# TT7-F_v1_5.net
KiCad netlist of a schematic drawn in EAGLE
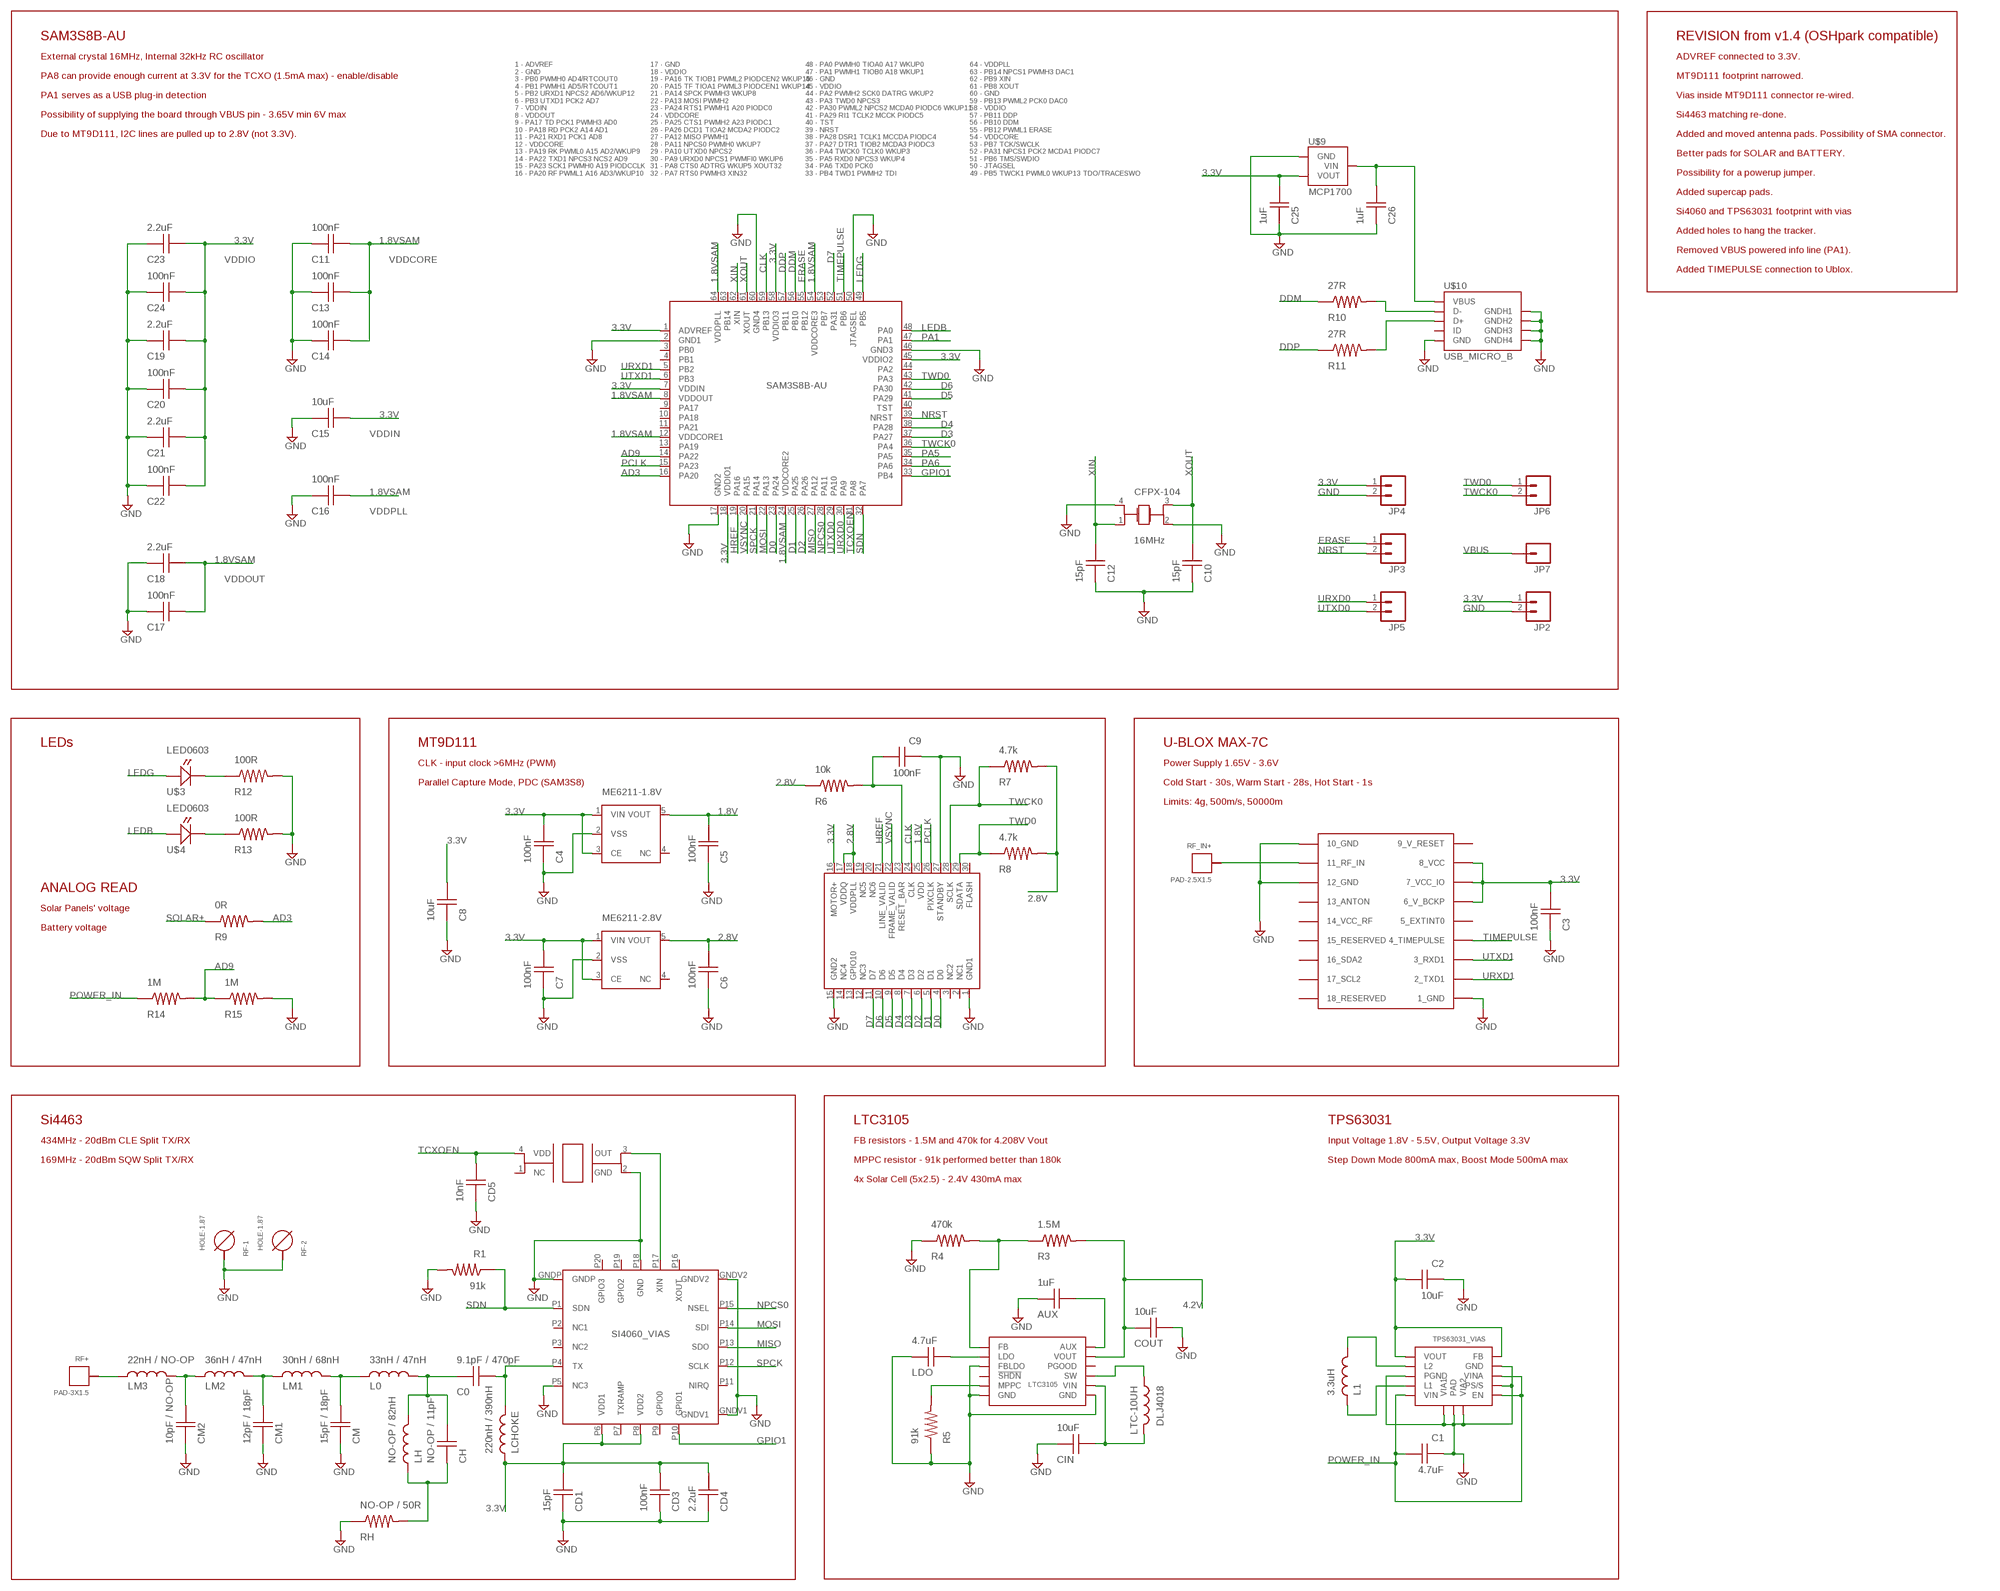
[diagram p0: schematic, sheet 1]

(export (version "E")
  (design (tool "Eeschema 10.0.6"))
  (components
    (comp (ref "AUX")
      (value "1uF")
      (footprint "eagle-import:CAP0603")
      (libsource (lib "eagle-import") (part "CAP0603"))
    )
    (comp (ref "C0")
      (value "9.1pF / 470pF")
      (footprint "eagle-import:CAP0402")
      (libsource (lib "eagle-import") (part "CAP0402"))
    )
    (comp (ref "C1")
      (value "4.7uF")
      (footprint "eagle-import:CAP0603")
      (libsource (lib "eagle-import") (part "CAP0603"))
    )
    (comp (ref "C2")
      (value "10uF")
      (footprint "eagle-import:CAP0805")
      (libsource (lib "eagle-import") (part "CAP0805"))
    )
    (comp (ref "C3")
      (value "100nF")
      (footprint "eagle-import:CAP0402")
      (libsource (lib "eagle-import") (part "CAP0402"))
    )
    (comp (ref "C4")
      (value "100nF")
      (footprint "eagle-import:CAP0402")
      (libsource (lib "eagle-import") (part "CAP0402"))
    )
    (comp (ref "C5")
      (value "100nF")
      (footprint "eagle-import:CAP0402")
      (libsource (lib "eagle-import") (part "CAP0402"))
    )
    (comp (ref "C6")
      (value "100nF")
      (footprint "eagle-import:CAP0402")
      (libsource (lib "eagle-import") (part "CAP0402"))
    )
    (comp (ref "C7")
      (value "100nF")
      (footprint "eagle-import:CAP0402")
      (libsource (lib "eagle-import") (part "CAP0402"))
    )
    (comp (ref "C8")
      (value "10uF")
      (footprint "eagle-import:CAP0805")
      (libsource (lib "eagle-import") (part "CAP0805"))
    )
    (comp (ref "C9")
      (value "100nF")
      (footprint "eagle-import:CAP0402")
      (libsource (lib "eagle-import") (part "CAP0402"))
    )
    (comp (ref "C10")
      (value "15pF")
      (footprint "eagle-import:CAP0402")
      (libsource (lib "eagle-import") (part "CAP0402"))
    )
    (comp (ref "C11")
      (value "100nF")
      (footprint "eagle-import:CAP0402")
      (libsource (lib "eagle-import") (part "CAP0402"))
    )
    (comp (ref "C12")
      (value "15pF")
      (footprint "eagle-import:CAP0402")
      (libsource (lib "eagle-import") (part "CAP0402"))
    )
    (comp (ref "C13")
      (value "100nF")
      (footprint "eagle-import:CAP0402")
      (libsource (lib "eagle-import") (part "CAP0402"))
    )
    (comp (ref "C14")
      (value "100nF")
      (footprint "eagle-import:CAP0402")
      (libsource (lib "eagle-import") (part "CAP0402"))
    )
    (comp (ref "C15")
      (value "10uF")
      (footprint "eagle-import:CAP0603")
      (libsource (lib "eagle-import") (part "CAP0603"))
    )
    (comp (ref "C16")
      (value "100nF")
      (footprint "eagle-import:CAP0402")
      (libsource (lib "eagle-import") (part "CAP0402"))
    )
    (comp (ref "C17")
      (value "100nF")
      (footprint "eagle-import:CAP0402")
      (libsource (lib "eagle-import") (part "CAP0402"))
    )
    (comp (ref "C18")
      (value "2.2uF")
      (footprint "eagle-import:CAP0402")
      (libsource (lib "eagle-import") (part "CAP0402"))
    )
    (comp (ref "C19")
      (value "2.2uF")
      (footprint "eagle-import:CAP0402")
      (libsource (lib "eagle-import") (part "CAP0402"))
    )
    (comp (ref "C20")
      (value "100nF")
      (footprint "eagle-import:CAP0402")
      (libsource (lib "eagle-import") (part "CAP0402"))
    )
    (comp (ref "C21")
      (value "2.2uF")
      (footprint "eagle-import:CAP0402")
      (libsource (lib "eagle-import") (part "CAP0402"))
    )
    (comp (ref "C22")
      (value "100nF")
      (footprint "eagle-import:CAP0402")
      (libsource (lib "eagle-import") (part "CAP0402"))
    )
    (comp (ref "C23")
      (value "2.2uF")
      (footprint "eagle-import:CAP0402")
      (libsource (lib "eagle-import") (part "CAP0402"))
    )
    (comp (ref "C24")
      (value "100nF")
      (footprint "eagle-import:CAP0402")
      (libsource (lib "eagle-import") (part "CAP0402"))
    )
    (comp (ref "C25")
      (value "1uF")
      (footprint "eagle-import:CAP0603")
      (libsource (lib "eagle-import") (part "CAP0603"))
    )
    (comp (ref "C26")
      (value "1uF")
      (footprint "eagle-import:CAP0603")
      (libsource (lib "eagle-import") (part "CAP0603"))
    )
    (comp (ref "CD1")
      (value "15pF")
      (footprint "eagle-import:CAP0402")
      (libsource (lib "eagle-import") (part "CAP0402"))
    )
    (comp (ref "CD3")
      (value "100nF")
      (footprint "eagle-import:CAP0402")
      (libsource (lib "eagle-import") (part "CAP0402"))
    )
    (comp (ref "CD4")
      (value "2.2uF")
      (footprint "eagle-import:CAP0402")
      (libsource (lib "eagle-import") (part "CAP0402"))
    )
    (comp (ref "CD5")
      (value "10nF")
      (footprint "eagle-import:CAP0402")
      (libsource (lib "eagle-import") (part "CAP0402"))
    )
    (comp (ref "CFPX-104")
      (value "16MHz")
      (footprint "eagle-import:CFPX-104")
      (libsource (lib "eagle-import") (part "CFPX-104"))
    )
    (comp (ref "CH")
      (value "NO-OP / 11pF")
      (footprint "eagle-import:CAP0402")
      (libsource (lib "eagle-import") (part "CAP0402"))
    )
    (comp (ref "CIN")
      (value "10uF")
      (footprint "eagle-import:CAP0603")
      (libsource (lib "eagle-import") (part "CAP0603"))
    )
    (comp (ref "CM")
      (value "15pF / 18pF")
      (footprint "eagle-import:CAP0402")
      (libsource (lib "eagle-import") (part "CAP0402"))
    )
    (comp (ref "CM1")
      (value "12pF / 18pF")
      (footprint "eagle-import:CAP0402")
      (libsource (lib "eagle-import") (part "CAP0402"))
    )
    (comp (ref "CM2")
      (value "10pF / NO-OP")
      (footprint "eagle-import:CAP0402")
      (libsource (lib "eagle-import") (part "CAP0402"))
    )
    (comp (ref "COUT")
      (value "10uF")
      (footprint "eagle-import:CAP0805")
      (libsource (lib "eagle-import") (part "CAP0805"))
    )
    (comp (ref "JP2")
      (value "M021X02_NO_SILK")
      (footprint "eagle-import:1X02_NO_SILK")
      (libsource (lib "eagle-import") (part "M021X02_NO_SILK"))
    )
    (comp (ref "JP3")
      (value "M021X02_NO_SILK")
      (footprint "eagle-import:1X02_NO_SILK")
      (libsource (lib "eagle-import") (part "M021X02_NO_SILK"))
    )
    (comp (ref "JP4")
      (value "M021X02_NO_SILK")
      (footprint "eagle-import:1X02_NO_SILK")
      (libsource (lib "eagle-import") (part "M021X02_NO_SILK"))
    )
    (comp (ref "JP5")
      (value "M021X02_NO_SILK")
      (footprint "eagle-import:1X02_NO_SILK")
      (libsource (lib "eagle-import") (part "M021X02_NO_SILK"))
    )
    (comp (ref "JP6")
      (value "M021X02_NO_SILK")
      (footprint "eagle-import:1X02_NO_SILK")
      (libsource (lib "eagle-import") (part "M021X02_NO_SILK"))
    )
    (comp (ref "JP7")
      (value "M01PTH_NO_SILK_YES_STOP")
      (footprint "eagle-import:1X01_NO_SILK")
      (libsource (lib "eagle-import") (part "M01PTH_NO_SILK_YES_STOP"))
    )
    (comp (ref "L0")
      (value "33nH / 47nH")
      (footprint "eagle-import:IND0402")
      (libsource (lib "eagle-import") (part "IND0402"))
    )
    (comp (ref "L1")
      (value "3.3uH")
      (footprint "eagle-import:DLJ3015")
      (libsource (lib "eagle-import") (part "DLJ3015"))
    )
    (comp (ref "LCHOKE")
      (value "220nH / 390nH")
      (footprint "eagle-import:IND0402")
      (libsource (lib "eagle-import") (part "IND0402"))
    )
    (comp (ref "LDO")
      (value "4.7uF")
      (footprint "eagle-import:CAP0603")
      (libsource (lib "eagle-import") (part "CAP0603"))
    )
    (comp (ref "LH")
      (value "NO-OP / 82nH")
      (footprint "eagle-import:IND0402")
      (libsource (lib "eagle-import") (part "IND0402"))
    )
    (comp (ref "LM1")
      (value "30nH / 68nH")
      (footprint "eagle-import:IND0402")
      (libsource (lib "eagle-import") (part "IND0402"))
    )
    (comp (ref "LM2")
      (value "36nH / 47nH")
      (footprint "eagle-import:IND0402")
      (libsource (lib "eagle-import") (part "IND0402"))
    )
    (comp (ref "LM3")
      (value "22nH / NO-OP")
      (footprint "eagle-import:IND0402")
      (libsource (lib "eagle-import") (part "IND0402"))
    )
    (comp (ref "LTC-10UH")
      (value "DLJ4018")
      (footprint "eagle-import:DLJ4018")
      (libsource (lib "eagle-import") (part "DLJ4018"))
    )
    (comp (ref "ME6211-1.8V")
      (value "ME6211_NEW")
      (footprint "eagle-import:ME6211_NEW")
      (libsource (lib "eagle-import") (part "ME6211_NEW"))
    )
    (comp (ref "ME6211-2.8V")
      (value "ME6211_NEW")
      (footprint "eagle-import:ME6211_NEW")
      (libsource (lib "eagle-import") (part "ME6211_NEW"))
    )
    (comp (ref "R1")
      (value "91k")
      (footprint "eagle-import:RES0402")
      (libsource (lib "eagle-import") (part "RES0402"))
    )
    (comp (ref "R3")
      (value "1.5M")
      (footprint "eagle-import:RES0402")
      (libsource (lib "eagle-import") (part "RES0402"))
    )
    (comp (ref "R4")
      (value "470k")
      (footprint "eagle-import:RES0402")
      (libsource (lib "eagle-import") (part "RES0402"))
    )
    (comp (ref "R5")
      (value "91k")
      (footprint "eagle-import:RES0402")
      (libsource (lib "eagle-import") (part "RES0402"))
    )
    (comp (ref "R6")
      (value "10k")
      (footprint "eagle-import:RES0402")
      (libsource (lib "eagle-import") (part "RES0402"))
    )
    (comp (ref "R7")
      (value "4.7k")
      (footprint "eagle-import:RES0402")
      (libsource (lib "eagle-import") (part "RES0402"))
    )
    (comp (ref "R8")
      (value "4.7k")
      (footprint "eagle-import:RES0402")
      (libsource (lib "eagle-import") (part "RES0402"))
    )
    (comp (ref "R9")
      (value "0R")
      (footprint "eagle-import:RES0402")
      (libsource (lib "eagle-import") (part "RES0402"))
    )
    (comp (ref "R10")
      (value "27R")
      (footprint "eagle-import:RES0402")
      (libsource (lib "eagle-import") (part "RES0402"))
    )
    (comp (ref "R11")
      (value "27R")
      (footprint "eagle-import:RES0402")
      (libsource (lib "eagle-import") (part "RES0402"))
    )
    (comp (ref "R12")
      (value "100R")
      (footprint "eagle-import:RES0402")
      (libsource (lib "eagle-import") (part "RES0402"))
    )
    (comp (ref "R13")
      (value "100R")
      (footprint "eagle-import:RES0402")
      (libsource (lib "eagle-import") (part "RES0402"))
    )
    (comp (ref "R14")
      (value "1M")
      (footprint "eagle-import:RES0603")
      (libsource (lib "eagle-import") (part "RES0603"))
    )
    (comp (ref "R15")
      (value "1M")
      (footprint "eagle-import:RES0603")
      (libsource (lib "eagle-import") (part "RES0603"))
    )
    (comp (ref "RF+")
      (value "PAD-3X1.5")
      (footprint "eagle-import:PAD-3X1.5")
      (libsource (lib "eagle-import") (part "PAD-3X1.5"))
    )
    (comp (ref "RF-1")
      (value "HOLE-1.87")
      (footprint "eagle-import:HOLE-1.87")
      (libsource (lib "eagle-import") (part "HOLE-1.87"))
    )
    (comp (ref "RF-2")
      (value "HOLE-1.87")
      (footprint "eagle-import:HOLE-1.87")
      (libsource (lib "eagle-import") (part "HOLE-1.87"))
    )
    (comp (ref "RF_IN+")
      (value "PAD-2.5X1.5")
      (footprint "eagle-import:PAD-2.5X1.5")
      (libsource (lib "eagle-import") (part "PAD-2.5X1.5"))
    )
    (comp (ref "RH")
      (value "NO-OP / 50R")
      (footprint "eagle-import:RES0402")
      (libsource (lib "eagle-import") (part "RES0402"))
    )
    (comp (ref "TCXO")
      (value "32MHz")
      (footprint "eagle-import:I547-2P3_TCXO")
      (libsource (lib "eagle-import") (part "I547-2P3_TCXO"))
    )
    (comp (ref "U$1")
      (value "SI4060_VIAS")
      (footprint "eagle-import:SI4060_VIAS")
      (libsource (lib "eagle-import") (part "SI4060_VIAS"))
    )
    (comp (ref "U$2")
      (value "UBLOX_MAX-7C")
      (footprint "eagle-import:UBLOX_MAX-7C")
      (libsource (lib "eagle-import") (part "UBLOX_MAX-7C"))
    )
    (comp (ref "U$3")
      (value "LED0603")
      (footprint "eagle-import:LED0603")
      (libsource (lib "eagle-import") (part "LED0603"))
    )
    (comp (ref "U$4")
      (value "LED0603")
      (footprint "eagle-import:LED0603")
      (libsource (lib "eagle-import") (part "LED0603"))
    )
    (comp (ref "U$9")
      (value "MCP1700")
      (footprint "eagle-import:MCP1700")
      (libsource (lib "eagle-import") (part "MCP1700"))
    )
    (comp (ref "U$10")
      (value "USB_MICRO_B")
      (footprint "eagle-import:USB_MICRO_B")
      (libsource (lib "eagle-import") (part "USB_MICRO_B"))
    )
    (comp (ref "U$15")
      (value "MT9D111-AVX145602-NEW")
      (footprint "eagle-import:MT9D111-AVX145602-NEW")
      (libsource (lib "eagle-import") (part "MT9D111-AVX145602-NEW"))
    )
    (comp (ref "U1")
      (value "LTC3105")
      (footprint "eagle-import:LTC3105")
      (libsource (lib "eagle-import") (part "LTC3105"))
    )
    (comp (ref "U3")
      (value "TPS63031_VIAS")
      (footprint "eagle-import:TPS63031_VIAS")
      (libsource (lib "eagle-import") (part "TPS63031_VIAS"))
    )
    (comp (ref "U4")
      (value "SAM3S8B-AU")
      (footprint "eagle-import:SAM3S8B-AU")
      (libsource (lib "eagle-import") (part "SAM3S8B-AU"))
    )
  )
  (nets
    (net (code "1") (name "/1.8V") (class "Default")
      (node (ref "C5") (pin "P$2") (pinfunction "P$2_P$2") (pintype "bidirectional"))
      (node (ref "ME6211-1.8V") (pin "5") (pinfunction "VOUT_5") (pintype "bidirectional"))
      (node (ref "U$15") (pin "25") (pinfunction "VDD_25") (pintype "bidirectional"))
    )
    (net (code "2") (name "/1.8VSAM") (class "Default")
      (node (ref "C11") (pin "P$2") (pinfunction "P$2_P$2") (pintype "bidirectional"))
      (node (ref "C13") (pin "P$2") (pinfunction "P$2_P$2") (pintype "bidirectional"))
      (node (ref "C14") (pin "P$2") (pinfunction "P$2_P$2") (pintype "bidirectional"))
      (node (ref "C16") (pin "P$2") (pinfunction "P$2_P$2") (pintype "bidirectional"))
      (node (ref "C17") (pin "P$2") (pinfunction "P$2_P$2") (pintype "bidirectional"))
      (node (ref "C18") (pin "P$2") (pinfunction "P$2_P$2") (pintype "bidirectional"))
      (node (ref "U4") (pin "12") (pinfunction "VDDCORE1_12") (pintype "bidirectional"))
      (node (ref "U4") (pin "24") (pinfunction "VDDCORE2_24") (pintype "bidirectional"))
      (node (ref "U4") (pin "54") (pinfunction "VDDCORE3_54") (pintype "bidirectional"))
      (node (ref "U4") (pin "64") (pinfunction "VDDPLL_64") (pintype "bidirectional"))
      (node (ref "U4") (pin "8") (pinfunction "VDDOUT_8") (pintype "bidirectional"))
    )
    (net (code "3") (name "/2.8V") (class "Default")
      (node (ref "C6") (pin "P$2") (pinfunction "P$2_P$2") (pintype "bidirectional"))
      (node (ref "ME6211-2.8V") (pin "5") (pinfunction "VOUT_5") (pintype "bidirectional"))
      (node (ref "R6") (pin "P$1") (pinfunction "P$1_P$1") (pintype "bidirectional"))
      (node (ref "R7") (pin "P$2") (pinfunction "P$2_P$2") (pintype "bidirectional"))
      (node (ref "R8") (pin "P$2") (pinfunction "P$2_P$2") (pintype "bidirectional"))
      (node (ref "U$15") (pin "17") (pinfunction "VDDQ_17") (pintype "bidirectional"))
      (node (ref "U$15") (pin "18") (pinfunction "VDDPLL_18") (pintype "bidirectional"))
    )
    (net (code "4") (name "/3.3V") (class "Default")
      (node (ref "C15") (pin "P$2") (pinfunction "P$2_P$2") (pintype "bidirectional"))
      (node (ref "C19") (pin "P$2") (pinfunction "P$2_P$2") (pintype "bidirectional"))
      (node (ref "C2") (pin "P$2") (pinfunction "P$2_P$2") (pintype "bidirectional"))
      (node (ref "C20") (pin "P$2") (pinfunction "P$2_P$2") (pintype "bidirectional"))
      (node (ref "C21") (pin "P$2") (pinfunction "P$2_P$2") (pintype "bidirectional"))
      (node (ref "C22") (pin "P$2") (pinfunction "P$2_P$2") (pintype "bidirectional"))
      (node (ref "C23") (pin "P$2") (pinfunction "P$2_P$2") (pintype "bidirectional"))
      (node (ref "C24") (pin "P$2") (pinfunction "P$2_P$2") (pintype "bidirectional"))
      (node (ref "C25") (pin "P$2") (pinfunction "P$2_P$2") (pintype "bidirectional"))
      (node (ref "C3") (pin "P$2") (pinfunction "P$2_P$2") (pintype "bidirectional"))
      (node (ref "C4") (pin "P$2") (pinfunction "P$2_P$2") (pintype "bidirectional"))
      (node (ref "C7") (pin "P$2") (pinfunction "P$2_P$2") (pintype "bidirectional"))
      (node (ref "C8") (pin "P$2") (pinfunction "P$2_P$2") (pintype "bidirectional"))
      (node (ref "CD1") (pin "P$2") (pinfunction "P$2_P$2") (pintype "bidirectional"))
      (node (ref "CD3") (pin "P$2") (pinfunction "P$2_P$2") (pintype "bidirectional"))
      (node (ref "CD4") (pin "P$2") (pinfunction "P$2_P$2") (pintype "bidirectional"))
      (node (ref "JP2") (pin "1") (pinfunction "1_1") (pintype "passive"))
      (node (ref "JP4") (pin "1") (pinfunction "1_1") (pintype "passive"))
      (node (ref "LCHOKE") (pin "P$1") (pinfunction "P$1_P$1") (pintype "bidirectional"))
      (node (ref "ME6211-1.8V") (pin "1") (pinfunction "VIN_1") (pintype "bidirectional"))
      (node (ref "ME6211-1.8V") (pin "3") (pinfunction "CE_3") (pintype "bidirectional"))
      (node (ref "ME6211-2.8V") (pin "1") (pinfunction "VIN_1") (pintype "bidirectional"))
      (node (ref "ME6211-2.8V") (pin "3") (pinfunction "CE_3") (pintype "bidirectional"))
      (node (ref "U$1") (pin "P6") (pinfunction "VDD1_P6") (pintype "bidirectional"))
      (node (ref "U$1") (pin "P8") (pinfunction "VDD2_P8") (pintype "bidirectional"))
      (node (ref "U$15") (pin "16") (pinfunction "MOTOR+_16") (pintype "bidirectional"))
      (node (ref "U$2") (pin "6_V_BCKP") (pinfunction "6_V_BCKP_6_V_BCKP") (pintype "bidirectional"))
      (node (ref "U$2") (pin "7_VCC_IO") (pinfunction "7_VCC_IO_7_VCC_IO") (pintype "power_in"))
      (node (ref "U$2") (pin "8_VCC") (pinfunction "8_VCC_8_VCC") (pintype "power_in"))
      (node (ref "U$9") (pin "2") (pinfunction "VOUT_2") (pintype "bidirectional"))
      (node (ref "U3") (pin "1") (pinfunction "VOUT_1") (pintype "bidirectional"))
      (node (ref "U3") (pin "10") (pinfunction "FB_10") (pintype "bidirectional"))
      (node (ref "U4") (pin "1") (pinfunction "ADVREF_1") (pintype "bidirectional"))
      (node (ref "U4") (pin "18") (pinfunction "VDDIO1_18") (pintype "bidirectional"))
      (node (ref "U4") (pin "45") (pinfunction "VDDIO2_45") (pintype "bidirectional"))
      (node (ref "U4") (pin "58") (pinfunction "VDDIO3_58") (pintype "bidirectional"))
      (node (ref "U4") (pin "7") (pinfunction "VDDIN_7") (pintype "bidirectional"))
    )
    (net (code "5") (name "/4.2V") (class "Default")
      (node (ref "COUT") (pin "P$1") (pinfunction "P$1_P$1") (pintype "bidirectional"))
      (node (ref "R3") (pin "P$2") (pinfunction "P$2_P$2") (pintype "bidirectional"))
      (node (ref "U1") (pin "11") (pinfunction "VOUT_11") (pintype "bidirectional"))
    )
    (net (code "6") (name "/9_V_RESET") (class "Default")
      (node (ref "U$2") (pin "9_V_RESET") (pinfunction "9_V_RESET_9_V_RESET") (pintype "power_in"))
    )
    (net (code "7") (name "/AD3") (class "Default")
      (node (ref "R9") (pin "P$2") (pinfunction "P$2_P$2") (pintype "bidirectional"))
      (node (ref "U4") (pin "16") (pinfunction "PA20_16") (pintype "bidirectional"))
    )
    (net (code "8") (name "/AD9") (class "Default")
      (node (ref "R14") (pin "P$2") (pinfunction "P$2_P$2") (pintype "bidirectional"))
      (node (ref "R15") (pin "P$1") (pinfunction "P$1_P$1") (pintype "bidirectional"))
      (node (ref "U4") (pin "14") (pinfunction "PA22_14") (pintype "bidirectional"))
    )
    (net (code "9") (name "/CLK") (class "Default")
      (node (ref "U$15") (pin "24") (pinfunction "CLK_24") (pintype "bidirectional"))
      (node (ref "U4") (pin "59") (pinfunction "PB13_59") (pintype "bidirectional"))
    )
    (net (code "10") (name "/D0") (class "Default")
      (node (ref "U$15") (pin "4") (pinfunction "D0_4") (pintype "bidirectional"))
      (node (ref "U4") (pin "23") (pinfunction "PA24_23") (pintype "bidirectional"))
    )
    (net (code "11") (name "/D1") (class "Default")
      (node (ref "U$15") (pin "5") (pinfunction "D1_5") (pintype "bidirectional"))
      (node (ref "U4") (pin "25") (pinfunction "PA25_25") (pintype "bidirectional"))
    )
    (net (code "12") (name "/D2") (class "Default")
      (node (ref "U$15") (pin "6") (pinfunction "D2_6") (pintype "bidirectional"))
      (node (ref "U4") (pin "26") (pinfunction "PA26_26") (pintype "bidirectional"))
    )
    (net (code "13") (name "/D3") (class "Default")
      (node (ref "U$15") (pin "7") (pinfunction "D3_7") (pintype "bidirectional"))
      (node (ref "U4") (pin "37") (pinfunction "PA27_37") (pintype "bidirectional"))
    )
    (net (code "14") (name "/D4") (class "Default")
      (node (ref "U$15") (pin "8") (pinfunction "D4_8") (pintype "bidirectional"))
      (node (ref "U4") (pin "38") (pinfunction "PA28_38") (pintype "bidirectional"))
    )
    (net (code "15") (name "/D5") (class "Default")
      (node (ref "U$15") (pin "9") (pinfunction "D5_9") (pintype "bidirectional"))
      (node (ref "U4") (pin "41") (pinfunction "PA29_41") (pintype "bidirectional"))
    )
    (net (code "16") (name "/D6") (class "Default")
      (node (ref "U$15") (pin "10") (pinfunction "D6_10") (pintype "bidirectional"))
      (node (ref "U4") (pin "42") (pinfunction "PA30_42") (pintype "bidirectional"))
    )
    (net (code "17") (name "/D7") (class "Default")
      (node (ref "U$15") (pin "11") (pinfunction "D7_11") (pintype "bidirectional"))
      (node (ref "U4") (pin "52") (pinfunction "PA31_52") (pintype "bidirectional"))
    )
    (net (code "18") (name "/DDM") (class "Default")
      (node (ref "R10") (pin "P$1") (pinfunction "P$1_P$1") (pintype "bidirectional"))
      (node (ref "U4") (pin "56") (pinfunction "PB10_56") (pintype "bidirectional"))
    )
    (net (code "19") (name "/DDP") (class "Default")
      (node (ref "R11") (pin "P$1") (pinfunction "P$1_P$1") (pintype "bidirectional"))
      (node (ref "U4") (pin "57") (pinfunction "PB11_57") (pintype "bidirectional"))
    )
    (net (code "20") (name "/ERASE") (class "Default")
      (node (ref "JP3") (pin "1") (pinfunction "1_1") (pintype "passive"))
      (node (ref "U4") (pin "55") (pinfunction "PB12_55") (pintype "bidirectional"))
    )
    (net (code "21") (name "/GPIO1") (class "Default")
      (node (ref "U$1") (pin "P10") (pinfunction "GPIO1_P10") (pintype "bidirectional"))
      (node (ref "U4") (pin "33") (pinfunction "PB4_33") (pintype "bidirectional"))
    )
    (net (code "22") (name "/HREF") (class "Default")
      (node (ref "U$15") (pin "21") (pinfunction "LINE_VALID_21") (pintype "bidirectional"))
      (node (ref "U4") (pin "19") (pinfunction "PA16_19") (pintype "bidirectional"))
    )
    (net (code "23") (name "/LEDB") (class "Default")
      (node (ref "U$4") (pin "ANODE") (pinfunction "ANODE_ANODE") (pintype "bidirectional"))
      (node (ref "U4") (pin "48") (pinfunction "PA0_48") (pintype "bidirectional"))
    )
    (net (code "24") (name "/LEDG") (class "Default")
      (node (ref "U$3") (pin "ANODE") (pinfunction "ANODE_ANODE") (pintype "bidirectional"))
      (node (ref "U4") (pin "49") (pinfunction "PB5_49") (pintype "bidirectional"))
    )
    (net (code "25") (name "/MISO") (class "Default")
      (node (ref "U$1") (pin "P13") (pinfunction "SDO_P13") (pintype "bidirectional"))
      (node (ref "U4") (pin "27") (pinfunction "PA12_27") (pintype "bidirectional"))
    )
    (net (code "26") (name "/MOSI") (class "Default")
      (node (ref "U$1") (pin "P14") (pinfunction "SDI_P14") (pintype "bidirectional"))
      (node (ref "U4") (pin "22") (pinfunction "PA13_22") (pintype "bidirectional"))
    )
    (net (code "27") (name "/NPCS0") (class "Default")
      (node (ref "U$1") (pin "P15") (pinfunction "NSEL_P15") (pintype "bidirectional"))
      (node (ref "U4") (pin "28") (pinfunction "PA11_28") (pintype "bidirectional"))
    )
    (net (code "28") (name "/NRST") (class "Default")
      (node (ref "JP3") (pin "2") (pinfunction "2_2") (pintype "passive"))
      (node (ref "U4") (pin "39") (pinfunction "NRST_39") (pintype "bidirectional"))
    )
    (net (code "29") (name "/PA1") (class "Default")
      (node (ref "U4") (pin "47") (pinfunction "PA1_47") (pintype "bidirectional"))
    )
    (net (code "30") (name "/PA5") (class "Default")
      (node (ref "U4") (pin "35") (pinfunction "PA5_35") (pintype "bidirectional"))
    )
    (net (code "31") (name "/PA6") (class "Default")
      (node (ref "U4") (pin "34") (pinfunction "PA6_34") (pintype "bidirectional"))
    )
    (net (code "32") (name "/PCLK") (class "Default")
      (node (ref "U$15") (pin "26") (pinfunction "PIXCLK_26") (pintype "bidirectional"))
      (node (ref "U4") (pin "15") (pinfunction "PA23_15") (pintype "bidirectional"))
    )
    (net (code "33") (name "/POWER_IN") (class "Default")
      (node (ref "C1") (pin "P$2") (pinfunction "P$2_P$2") (pintype "bidirectional"))
      (node (ref "R14") (pin "P$1") (pinfunction "P$1_P$1") (pintype "bidirectional"))
      (node (ref "U3") (pin "5") (pinfunction "VIN_5") (pintype "bidirectional"))
      (node (ref "U3") (pin "6") (pinfunction "EN_6") (pintype "bidirectional"))
      (node (ref "U3") (pin "8") (pinfunction "VINA_8") (pintype "bidirectional"))
    )
    (net (code "34") (name "/SDN") (class "Default")
      (node (ref "R1") (pin "P$1") (pinfunction "P$1_P$1") (pintype "bidirectional"))
      (node (ref "U$1") (pin "P1") (pinfunction "SDN_P1") (pintype "bidirectional"))
      (node (ref "U4") (pin "32") (pinfunction "PA7_32") (pintype "bidirectional"))
    )
    (net (code "35") (name "/SOLAR+") (class "Default")
      (node (ref "CIN") (pin "P$2") (pinfunction "P$2_P$2") (pintype "bidirectional"))
      (node (ref "LTC-10UH") (pin "P$2") (pinfunction "P$2_P$2") (pintype "bidirectional"))
      (node (ref "R9") (pin "P$1") (pinfunction "P$1_P$1") (pintype "bidirectional"))
      (node (ref "U1") (pin "8") (pinfunction "VIN_8") (pintype "bidirectional"))
    )
    (net (code "36") (name "/SPCK") (class "Default")
      (node (ref "U$1") (pin "P12") (pinfunction "SCLK_P12") (pintype "bidirectional"))
      (node (ref "U4") (pin "21") (pinfunction "PA14_21") (pintype "bidirectional"))
    )
    (net (code "37") (name "/TCXOEN") (class "Default")
      (node (ref "CD5") (pin "P$2") (pinfunction "P$2_P$2") (pintype "bidirectional"))
      (node (ref "TCXO") (pin "4") (pinfunction "VDD_4") (pintype "bidirectional"))
      (node (ref "U4") (pin "31") (pinfunction "PA8_31") (pintype "bidirectional"))
    )
    (net (code "38") (name "/TIMEPULSE") (class "Default")
      (node (ref "U$2") (pin "4_TIMEPULSE") (pinfunction "4_TIMEPULSE_4_TIMEPULSE") (pintype "bidirectional"))
      (node (ref "U4") (pin "51") (pinfunction "PB6_51") (pintype "bidirectional"))
    )
    (net (code "39") (name "/TWCK0") (class "Default")
      (node (ref "JP6") (pin "2") (pinfunction "2_2") (pintype "passive"))
      (node (ref "R7") (pin "P$1") (pinfunction "P$1_P$1") (pintype "bidirectional"))
      (node (ref "U$15") (pin "28") (pinfunction "SCLK_28") (pintype "bidirectional"))
      (node (ref "U4") (pin "36") (pinfunction "PA4_36") (pintype "bidirectional"))
    )
    (net (code "40") (name "/TWD0") (class "Default")
      (node (ref "JP6") (pin "1") (pinfunction "1_1") (pintype "passive"))
      (node (ref "R8") (pin "P$1") (pinfunction "P$1_P$1") (pintype "bidirectional"))
      (node (ref "U$15") (pin "29") (pinfunction "SDATA_29") (pintype "bidirectional"))
      (node (ref "U4") (pin "43") (pinfunction "PA3_43") (pintype "bidirectional"))
    )
    (net (code "41") (name "/URXD0") (class "Default")
      (node (ref "JP5") (pin "1") (pinfunction "1_1") (pintype "passive"))
      (node (ref "U4") (pin "30") (pinfunction "PA9_30") (pintype "bidirectional"))
    )
    (net (code "42") (name "/URXD1") (class "Default")
      (node (ref "U$2") (pin "2_TXD1") (pinfunction "2_TXD1_2_TXD1") (pintype "bidirectional"))
      (node (ref "U4") (pin "5") (pinfunction "PB2_5") (pintype "bidirectional"))
    )
    (net (code "43") (name "/UTXD0") (class "Default")
      (node (ref "JP5") (pin "2") (pinfunction "2_2") (pintype "passive"))
      (node (ref "U4") (pin "29") (pinfunction "PA10_29") (pintype "bidirectional"))
    )
    (net (code "44") (name "/UTXD1") (class "Default")
      (node (ref "U$2") (pin "3_RXD1") (pinfunction "3_RXD1_3_RXD1") (pintype "bidirectional"))
      (node (ref "U4") (pin "6") (pinfunction "PB3_6") (pintype "bidirectional"))
    )
    (net (code "45") (name "/VBUS") (class "Default")
      (node (ref "C26") (pin "P$2") (pinfunction "P$2_P$2") (pintype "bidirectional"))
      (node (ref "JP7") (pin "1") (pinfunction "1_1") (pintype "passive"))
      (node (ref "U$10") (pin "VBUS") (pinfunction "VBUS_VBUS") (pintype "bidirectional"))
      (node (ref "U$9") (pin "3") (pinfunction "VIN_3") (pintype "bidirectional"))
    )
    (net (code "46") (name "/VSYNC") (class "Default")
      (node (ref "U$15") (pin "22") (pinfunction "FRAME_VALID_22") (pintype "bidirectional"))
      (node (ref "U4") (pin "20") (pinfunction "PA15_20") (pintype "bidirectional"))
    )
    (net (code "47") (name "/XIN") (class "Default")
      (node (ref "C12") (pin "P$2") (pinfunction "P$2_P$2") (pintype "bidirectional"))
      (node (ref "CFPX-104") (pin "1") (pinfunction "XTAL1_1") (pintype "bidirectional"))
      (node (ref "U4") (pin "62") (pinfunction "XIN_62") (pintype "bidirectional"))
    )
    (net (code "48") (name "/XOUT") (class "Default")
      (node (ref "C10") (pin "P$2") (pinfunction "P$2_P$2") (pintype "bidirectional"))
      (node (ref "CFPX-104") (pin "3") (pinfunction "XTAL2_3") (pintype "bidirectional"))
      (node (ref "U4") (pin "61") (pinfunction "XOUT_61") (pintype "bidirectional"))
    )
    (net (code "49") (name "GND") (class "Default")
      (node (ref "AUX") (pin "P$1") (pinfunction "P$1_P$1") (pintype "bidirectional"))
      (node (ref "C1") (pin "P$1") (pinfunction "P$1_P$1") (pintype "bidirectional"))
      (node (ref "C10") (pin "P$1") (pinfunction "P$1_P$1") (pintype "bidirectional"))
      (node (ref "C11") (pin "P$1") (pinfunction "P$1_P$1") (pintype "bidirectional"))
      (node (ref "C12") (pin "P$1") (pinfunction "P$1_P$1") (pintype "bidirectional"))
      (node (ref "C13") (pin "P$1") (pinfunction "P$1_P$1") (pintype "bidirectional"))
      (node (ref "C14") (pin "P$1") (pinfunction "P$1_P$1") (pintype "bidirectional"))
      (node (ref "C15") (pin "P$1") (pinfunction "P$1_P$1") (pintype "bidirectional"))
      (node (ref "C16") (pin "P$1") (pinfunction "P$1_P$1") (pintype "bidirectional"))
      (node (ref "C17") (pin "P$1") (pinfunction "P$1_P$1") (pintype "bidirectional"))
      (node (ref "C18") (pin "P$1") (pinfunction "P$1_P$1") (pintype "bidirectional"))
      (node (ref "C19") (pin "P$1") (pinfunction "P$1_P$1") (pintype "bidirectional"))
      (node (ref "C2") (pin "P$1") (pinfunction "P$1_P$1") (pintype "bidirectional"))
      (node (ref "C20") (pin "P$1") (pinfunction "P$1_P$1") (pintype "bidirectional"))
      (node (ref "C21") (pin "P$1") (pinfunction "P$1_P$1") (pintype "bidirectional"))
      (node (ref "C22") (pin "P$1") (pinfunction "P$1_P$1") (pintype "bidirectional"))
      (node (ref "C23") (pin "P$1") (pinfunction "P$1_P$1") (pintype "bidirectional"))
      (node (ref "C24") (pin "P$1") (pinfunction "P$1_P$1") (pintype "bidirectional"))
      (node (ref "C25") (pin "P$1") (pinfunction "P$1_P$1") (pintype "bidirectional"))
      (node (ref "C26") (pin "P$1") (pinfunction "P$1_P$1") (pintype "bidirectional"))
      (node (ref "C3") (pin "P$1") (pinfunction "P$1_P$1") (pintype "bidirectional"))
      (node (ref "C4") (pin "P$1") (pinfunction "P$1_P$1") (pintype "bidirectional"))
      (node (ref "C5") (pin "P$1") (pinfunction "P$1_P$1") (pintype "bidirectional"))
      (node (ref "C6") (pin "P$1") (pinfunction "P$1_P$1") (pintype "bidirectional"))
      (node (ref "C7") (pin "P$1") (pinfunction "P$1_P$1") (pintype "bidirectional"))
      (node (ref "C8") (pin "P$1") (pinfunction "P$1_P$1") (pintype "bidirectional"))
      (node (ref "C9") (pin "P$1") (pinfunction "P$1_P$1") (pintype "bidirectional"))
      (node (ref "CD1") (pin "P$1") (pinfunction "P$1_P$1") (pintype "bidirectional"))
      (node (ref "CD3") (pin "P$1") (pinfunction "P$1_P$1") (pintype "bidirectional"))
      (node (ref "CD4") (pin "P$1") (pinfunction "P$1_P$1") (pintype "bidirectional"))
      (node (ref "CD5") (pin "P$1") (pinfunction "P$1_P$1") (pintype "bidirectional"))
      (node (ref "CFPX-104") (pin "2") (pinfunction "GND1_2") (pintype "bidirectional"))
      (node (ref "CFPX-104") (pin "4") (pinfunction "GND2_4") (pintype "bidirectional"))
      (node (ref "CIN") (pin "P$1") (pinfunction "P$1_P$1") (pintype "bidirectional"))
      (node (ref "CM") (pin "P$1") (pinfunction "P$1_P$1") (pintype "bidirectional"))
      (node (ref "CM1") (pin "P$1") (pinfunction "P$1_P$1") (pintype "bidirectional"))
      (node (ref "CM2") (pin "P$1") (pinfunction "P$1_P$1") (pintype "bidirectional"))
      (node (ref "COUT") (pin "P$2") (pinfunction "P$2_P$2") (pintype "bidirectional"))
      (node (ref "JP2") (pin "2") (pinfunction "2_2") (pintype "passive"))
      (node (ref "JP4") (pin "2") (pinfunction "2_2") (pintype "passive"))
      (node (ref "LDO") (pin "P$1") (pinfunction "P$1_P$1") (pintype "bidirectional"))
      (node (ref "ME6211-1.8V") (pin "2") (pinfunction "VSS_2") (pintype "bidirectional"))
      (node (ref "ME6211-2.8V") (pin "2") (pinfunction "VSS_2") (pintype "bidirectional"))
      (node (ref "R1") (pin "P$2") (pinfunction "P$2_P$2") (pintype "bidirectional"))
      (node (ref "R12") (pin "P$2") (pinfunction "P$2_P$2") (pintype "bidirectional"))
      (node (ref "R13") (pin "P$2") (pinfunction "P$2_P$2") (pintype "bidirectional"))
      (node (ref "R15") (pin "P$2") (pinfunction "P$2_P$2") (pintype "bidirectional"))
      (node (ref "R4") (pin "P$1") (pinfunction "P$1_P$1") (pintype "bidirectional"))
      (node (ref "R5") (pin "P$1") (pinfunction "P$1_P$1") (pintype "bidirectional"))
      (node (ref "RF-1") (pin "P$1") (pinfunction "P$1_P$1") (pintype "bidirectional"))
      (node (ref "RF-2") (pin "P$1") (pinfunction "P$1_P$1") (pintype "bidirectional"))
      (node (ref "RH") (pin "P$1") (pinfunction "P$1_P$1") (pintype "bidirectional"))
      (node (ref "TCXO") (pin "2") (pinfunction "GND_2") (pintype "bidirectional"))
      (node (ref "U$1") (pin "GNDP") (pinfunction "GNDP_GNDP") (pintype "bidirectional"))
      (node (ref "U$1") (pin "GNDV1") (pinfunction "GNDV1_GNDV1") (pintype "bidirectional"))
      (node (ref "U$1") (pin "GNDV2") (pinfunction "GNDV2_GNDV2") (pintype "bidirectional"))
      (node (ref "U$1") (pin "P18") (pinfunction "GND_P18") (pintype "bidirectional"))
      (node (ref "U$1") (pin "P5") (pinfunction "NC3_P5") (pintype "bidirectional"))
      (node (ref "U$10") (pin "GND") (pinfunction "GND_GND") (pintype "bidirectional"))
      (node (ref "U$10") (pin "P$6") (pinfunction "GNDH1_P$6") (pintype "bidirectional"))
      (node (ref "U$10") (pin "P$7") (pinfunction "GNDH2_P$7") (pintype "bidirectional"))
      (node (ref "U$10") (pin "P$8") (pinfunction "GNDH3_P$8") (pintype "bidirectional"))
      (node (ref "U$10") (pin "P$9") (pinfunction "GNDH4_P$9") (pintype "bidirectional"))
      (node (ref "U$15") (pin "1") (pinfunction "GND1_1") (pintype "bidirectional"))
      (node (ref "U$15") (pin "15") (pinfunction "GND2_15") (pintype "bidirectional"))
      (node (ref "U$15") (pin "27") (pinfunction "STANDBY_27") (pintype "bidirectional"))
      (node (ref "U$2") (pin "10_GND") (pinfunction "10_GND_10_GND") (pintype "power_in"))
      (node (ref "U$2") (pin "12_GND") (pinfunction "12_GND_12_GND") (pintype "power_in"))
      (node (ref "U$2") (pin "1_GND") (pinfunction "1_GND_1_GND") (pintype "power_in"))
      (node (ref "U$9") (pin "1") (pinfunction "GND_1") (pintype "bidirectional"))
      (node (ref "U1") (pin "3") (pinfunction "FBLDO_3") (pintype "bidirectional"))
      (node (ref "U1") (pin "6") (pinfunction "GND_6") (pintype "bidirectional"))
      (node (ref "U1") (pin "7") (pinfunction "GND_7") (pintype "bidirectional"))
      (node (ref "U3") (pin "11") (pinfunction "PAD_11") (pintype "bidirectional"))
      (node (ref "U3") (pin "3") (pinfunction "PGND_3") (pintype "bidirectional"))
      (node (ref "U3") (pin "7") (pinfunction "PS/S_7") (pintype "bidirectional"))
      (node (ref "U3") (pin "9") (pinfunction "GND_9") (pintype "bidirectional"))
      (node (ref "U3") (pin "VIA1") (pinfunction "VIA1_VIA1") (pintype "bidirectional"))
      (node (ref "U3") (pin "VIA2") (pinfunction "VIA2_VIA2") (pintype "bidirectional"))
      (node (ref "U4") (pin "17") (pinfunction "GND2_17") (pintype "bidirectional"))
      (node (ref "U4") (pin "2") (pinfunction "GND1_2") (pintype "bidirectional"))
      (node (ref "U4") (pin "46") (pinfunction "GND3_46") (pintype "bidirectional"))
      (node (ref "U4") (pin "50") (pinfunction "JTAGSEL_50") (pintype "bidirectional"))
      (node (ref "U4") (pin "60") (pinfunction "GND4_60") (pintype "bidirectional"))
    )
    (net (code "50") (name "Net-(C0-PadP$1)") (class "Default")
      (node (ref "C0") (pin "P$1") (pinfunction "P$1_P$1") (pintype "bidirectional"))
      (node (ref "CH") (pin "P$2") (pinfunction "P$2_P$2") (pintype "bidirectional"))
      (node (ref "L0") (pin "P$2") (pinfunction "P$2_P$2") (pintype "bidirectional"))
      (node (ref "LH") (pin "P$2") (pinfunction "P$2_P$2") (pintype "bidirectional"))
    )
    (net (code "51") (name "Net-(CH-PadP$1)") (class "Default")
      (node (ref "CH") (pin "P$1") (pinfunction "P$1_P$1") (pintype "bidirectional"))
      (node (ref "LH") (pin "P$1") (pinfunction "P$1_P$1") (pintype "bidirectional"))
      (node (ref "RH") (pin "P$2") (pinfunction "P$2_P$2") (pintype "bidirectional"))
    )
    (net (code "52") (name "Net-(CM-PadP$2)") (class "Default")
      (node (ref "CM") (pin "P$2") (pinfunction "P$2_P$2") (pintype "bidirectional"))
      (node (ref "L0") (pin "P$1") (pinfunction "P$1_P$1") (pintype "bidirectional"))
      (node (ref "LM1") (pin "P$2") (pinfunction "P$2_P$2") (pintype "bidirectional"))
    )
    (net (code "53") (name "Net-(CM1-PadP$2)") (class "Default")
      (node (ref "CM1") (pin "P$2") (pinfunction "P$2_P$2") (pintype "bidirectional"))
      (node (ref "LM1") (pin "P$1") (pinfunction "P$1_P$1") (pintype "bidirectional"))
      (node (ref "LM2") (pin "P$2") (pinfunction "P$2_P$2") (pintype "bidirectional"))
    )
    (net (code "54") (name "Net-(CM2-PadP$2)") (class "Default")
      (node (ref "CM2") (pin "P$2") (pinfunction "P$2_P$2") (pintype "bidirectional"))
      (node (ref "LM2") (pin "P$1") (pinfunction "P$1_P$1") (pintype "bidirectional"))
      (node (ref "LM3") (pin "P$2") (pinfunction "P$2_P$2") (pintype "bidirectional"))
    )
    (net (code "55") (name "Net-(LM3-PadP$1)") (class "Default")
      (node (ref "LM3") (pin "P$1") (pinfunction "P$1_P$1") (pintype "bidirectional"))
      (node (ref "RF+") (pin "P$1") (pinfunction "P$1_P$1") (pintype "bidirectional"))
    )
    (net (code "56") (name "Net-(R10-PadP$2)") (class "Default")
      (node (ref "R10") (pin "P$2") (pinfunction "P$2_P$2") (pintype "bidirectional"))
      (node (ref "U$10") (pin "D-") (pinfunction "D-_D-") (pintype "bidirectional"))
    )
    (net (code "57") (name "Net-(R11-PadP$2)") (class "Default")
      (node (ref "R11") (pin "P$2") (pinfunction "P$2_P$2") (pintype "bidirectional"))
      (node (ref "U$10") (pin "D+") (pinfunction "D+_D+") (pintype "bidirectional"))
    )
    (net (code "58") (name "Net-(R12-PadP$1)") (class "Default")
      (node (ref "R12") (pin "P$1") (pinfunction "P$1_P$1") (pintype "bidirectional"))
      (node (ref "U$3") (pin "CATHODE") (pinfunction "CATHODE_CATHODE") (pintype "bidirectional"))
    )
    (net (code "59") (name "Net-(R13-PadP$1)") (class "Default")
      (node (ref "R13") (pin "P$1") (pinfunction "P$1_P$1") (pintype "bidirectional"))
      (node (ref "U$4") (pin "CATHODE") (pinfunction "CATHODE_CATHODE") (pintype "bidirectional"))
    )
    (net (code "60") (name "Net-(RF_IN+-PadP$1)") (class "Default")
      (node (ref "RF_IN+") (pin "P$1") (pinfunction "P$1_P$1") (pintype "bidirectional"))
      (node (ref "U$2") (pin "11_RF_IN") (pinfunction "11_RF_IN_11_RF_IN") (pintype "bidirectional"))
    )
    (net (code "61") (name "Net-(TCXO-OUT)") (class "Default")
      (node (ref "TCXO") (pin "3") (pinfunction "OUT_3") (pintype "bidirectional"))
      (node (ref "U$1") (pin "P17") (pinfunction "XIN_P17") (pintype "bidirectional"))
    )
    (net (code "62") (name "Net-(U$1-TX)") (class "Default")
      (node (ref "C0") (pin "P$2") (pinfunction "P$2_P$2") (pintype "bidirectional"))
      (node (ref "LCHOKE") (pin "P$2") (pinfunction "P$2_P$2") (pintype "bidirectional"))
      (node (ref "U$1") (pin "P4") (pinfunction "TX_P4") (pintype "bidirectional"))
    )
    (net (code "63") (name "Net-(U$15-RESET_BAR)") (class "Default")
      (node (ref "C9") (pin "P$2") (pinfunction "P$2_P$2") (pintype "bidirectional"))
      (node (ref "R6") (pin "P$2") (pinfunction "P$2_P$2") (pintype "bidirectional"))
      (node (ref "U$15") (pin "23") (pinfunction "RESET_BAR_23") (pintype "bidirectional"))
    )
    (net (code "64") (name "Net-(U1-AUX)") (class "Default")
      (node (ref "AUX") (pin "P$2") (pinfunction "P$2_P$2") (pintype "bidirectional"))
      (node (ref "U1") (pin "12") (pinfunction "AUX_12") (pintype "bidirectional"))
    )
    (net (code "65") (name "Net-(U1-FB)") (class "Default")
      (node (ref "R3") (pin "P$1") (pinfunction "P$1_P$1") (pintype "bidirectional"))
      (node (ref "R4") (pin "P$2") (pinfunction "P$2_P$2") (pintype "bidirectional"))
      (node (ref "U1") (pin "1") (pinfunction "FB_1") (pintype "bidirectional"))
    )
    (net (code "66") (name "Net-(U1-LDO)") (class "Default")
      (node (ref "LDO") (pin "P$2") (pinfunction "P$2_P$2") (pintype "bidirectional"))
      (node (ref "U1") (pin "2") (pinfunction "LDO_2") (pintype "bidirectional"))
    )
    (net (code "67") (name "Net-(U1-MPPC)") (class "Default")
      (node (ref "R5") (pin "P$2") (pinfunction "P$2_P$2") (pintype "bidirectional"))
      (node (ref "U1") (pin "5") (pinfunction "MPPC_5") (pintype "bidirectional"))
    )
    (net (code "68") (name "Net-(U1-SW)") (class "Default")
      (node (ref "LTC-10UH") (pin "P$1") (pinfunction "P$1_P$1") (pintype "bidirectional"))
      (node (ref "U1") (pin "9") (pinfunction "SW_9") (pintype "bidirectional"))
    )
    (net (code "69") (name "Net-(U3-L1)") (class "Default")
      (node (ref "L1") (pin "P$1") (pinfunction "P$1_P$1") (pintype "bidirectional"))
      (node (ref "U3") (pin "4") (pinfunction "L1_4") (pintype "bidirectional"))
    )
    (net (code "70") (name "Net-(U3-L2)") (class "Default")
      (node (ref "L1") (pin "P$2") (pinfunction "P$2_P$2") (pintype "bidirectional"))
      (node (ref "U3") (pin "2") (pinfunction "L2_2") (pintype "bidirectional"))
    )
    (net (code "71") (name "unconnected-(ME6211-1.8V-NC-Pad4)") (class "Default")
      (node (ref "ME6211-1.8V") (pin "4") (pinfunction "NC_4") (pintype "bidirectional"))
    )
    (net (code "72") (name "unconnected-(ME6211-2.8V-NC-Pad4)") (class "Default")
      (node (ref "ME6211-2.8V") (pin "4") (pinfunction "NC_4") (pintype "bidirectional"))
    )
    (net (code "73") (name "unconnected-(TCXO-NC-Pad1)") (class "Default")
      (node (ref "TCXO") (pin "1") (pinfunction "NC_1") (pintype "bidirectional"))
    )
    (net (code "74") (name "unconnected-(U$1-GPIO0-PadP9)") (class "Default")
      (node (ref "U$1") (pin "P9") (pinfunction "GPIO0_P9") (pintype "bidirectional"))
    )
    (net (code "75") (name "unconnected-(U$1-GPIO2-PadP19)") (class "Default")
      (node (ref "U$1") (pin "P19") (pinfunction "GPIO2_P19") (pintype "bidirectional"))
    )
    (net (code "76") (name "unconnected-(U$1-GPIO3-PadP20)") (class "Default")
      (node (ref "U$1") (pin "P20") (pinfunction "GPIO3_P20") (pintype "bidirectional"))
    )
    (net (code "77") (name "unconnected-(U$1-NC1-PadP2)") (class "Default")
      (node (ref "U$1") (pin "P2") (pinfunction "NC1_P2") (pintype "bidirectional"))
    )
    (net (code "78") (name "unconnected-(U$1-NC2-PadP3)") (class "Default")
      (node (ref "U$1") (pin "P3") (pinfunction "NC2_P3") (pintype "bidirectional"))
    )
    (net (code "79") (name "unconnected-(U$1-NIRQ-PadP11)") (class "Default")
      (node (ref "U$1") (pin "P11") (pinfunction "NIRQ_P11") (pintype "bidirectional"))
    )
    (net (code "80") (name "unconnected-(U$1-TXRAMP-PadP7)") (class "Default")
      (node (ref "U$1") (pin "P7") (pinfunction "TXRAMP_P7") (pintype "bidirectional"))
    )
    (net (code "81") (name "unconnected-(U$1-XOUT-PadP16)") (class "Default")
      (node (ref "U$1") (pin "P16") (pinfunction "XOUT_P16") (pintype "bidirectional"))
    )
    (net (code "82") (name "unconnected-(U$2-Pad5_EXTINT0)") (class "Default")
      (node (ref "U$2") (pin "5_EXTINT0") (pinfunction "5_EXTINT0_5_EXTINT0") (pintype "bidirectional"))
    )
    (net (code "83") (name "unconnected-(U$2-Pad13_ANTON)") (class "Default")
      (node (ref "U$2") (pin "13_ANTON") (pinfunction "13_ANTON_13_ANTON") (pintype "bidirectional"))
    )
    (net (code "84") (name "unconnected-(U$2-Pad14_VCC_RF)") (class "Default")
      (node (ref "U$2") (pin "14_VCC_RF") (pinfunction "14_VCC_RF_14_VCC_RF") (pintype "bidirectional"))
    )
    (net (code "85") (name "unconnected-(U$2-Pad15_RESERVED)") (class "Default")
      (node (ref "U$2") (pin "15_RESERVED") (pinfunction "15_RESERVED_15_RESERVED") (pintype "bidirectional"))
    )
    (net (code "86") (name "unconnected-(U$2-Pad16_SDA2)") (class "Default")
      (node (ref "U$2") (pin "16_SDA2") (pinfunction "16_SDA2_16_SDA2") (pintype "bidirectional"))
    )
    (net (code "87") (name "unconnected-(U$2-Pad17_SCL2)") (class "Default")
      (node (ref "U$2") (pin "17_SCL2") (pinfunction "17_SCL2_17_SCL2") (pintype "bidirectional"))
    )
    (net (code "88") (name "unconnected-(U$2-Pad18_RESERVED)") (class "Default")
      (node (ref "U$2") (pin "18_RESERVED") (pinfunction "18_RESERVED_18_RESERVED") (pintype "bidirectional"))
    )
    (net (code "89") (name "unconnected-(U$10-PadID)") (class "Default")
      (node (ref "U$10") (pin "ID") (pinfunction "ID_ID") (pintype "bidirectional"))
    )
    (net (code "90") (name "unconnected-(U$15-FLASH-Pad30)") (class "Default")
      (node (ref "U$15") (pin "30") (pinfunction "FLASH_30") (pintype "bidirectional"))
    )
    (net (code "91") (name "unconnected-(U$15-GPIO10-Pad13)") (class "Default")
      (node (ref "U$15") (pin "13") (pinfunction "GPIO10_13") (pintype "bidirectional"))
    )
    (net (code "92") (name "unconnected-(U$15-NC1-Pad2)") (class "Default")
      (node (ref "U$15") (pin "2") (pinfunction "NC1_2") (pintype "bidirectional"))
    )
    (net (code "93") (name "unconnected-(U$15-NC2-Pad3)") (class "Default")
      (node (ref "U$15") (pin "3") (pinfunction "NC2_3") (pintype "bidirectional"))
    )
    (net (code "94") (name "unconnected-(U$15-NC3-Pad12)") (class "Default")
      (node (ref "U$15") (pin "12") (pinfunction "NC3_12") (pintype "bidirectional"))
    )
    (net (code "95") (name "unconnected-(U$15-NC4-Pad14)") (class "Default")
      (node (ref "U$15") (pin "14") (pinfunction "NC4_14") (pintype "bidirectional"))
    )
    (net (code "96") (name "unconnected-(U$15-NC5-Pad19)") (class "Default")
      (node (ref "U$15") (pin "19") (pinfunction "NC5_19") (pintype "bidirectional"))
    )
    (net (code "97") (name "unconnected-(U$15-NC6-Pad20)") (class "Default")
      (node (ref "U$15") (pin "20") (pinfunction "NC6_20") (pintype "bidirectional"))
    )
    (net (code "98") (name "unconnected-(U1-PGOOD-Pad10)") (class "Default")
      (node (ref "U1") (pin "10") (pinfunction "PGOOD_10") (pintype "bidirectional"))
    )
    (net (code "99") (name "unconnected-(U1-~{SHDN}-Pad4)") (class "Default")
      (node (ref "U1") (pin "4") (pinfunction "~{SHDN}_4") (pintype "bidirectional"))
    )
    (net (code "100") (name "unconnected-(U4-PA2-Pad44)") (class "Default")
      (node (ref "U4") (pin "44") (pinfunction "PA2_44") (pintype "bidirectional"))
    )
    (net (code "101") (name "unconnected-(U4-PA17-Pad9)") (class "Default")
      (node (ref "U4") (pin "9") (pinfunction "PA17_9") (pintype "bidirectional"))
    )
    (net (code "102") (name "unconnected-(U4-PA18-Pad10)") (class "Default")
      (node (ref "U4") (pin "10") (pinfunction "PA18_10") (pintype "bidirectional"))
    )
    (net (code "103") (name "unconnected-(U4-PA19-Pad13)") (class "Default")
      (node (ref "U4") (pin "13") (pinfunction "PA19_13") (pintype "bidirectional"))
    )
    (net (code "104") (name "unconnected-(U4-PA21-Pad11)") (class "Default")
      (node (ref "U4") (pin "11") (pinfunction "PA21_11") (pintype "bidirectional"))
    )
    (net (code "105") (name "unconnected-(U4-PB0-Pad3)") (class "Default")
      (node (ref "U4") (pin "3") (pinfunction "PB0_3") (pintype "bidirectional"))
    )
    (net (code "106") (name "unconnected-(U4-PB1-Pad4)") (class "Default")
      (node (ref "U4") (pin "4") (pinfunction "PB1_4") (pintype "bidirectional"))
    )
    (net (code "107") (name "unconnected-(U4-PB7-Pad53)") (class "Default")
      (node (ref "U4") (pin "53") (pinfunction "PB7_53") (pintype "bidirectional"))
    )
    (net (code "108") (name "unconnected-(U4-PB14-Pad63)") (class "Default")
      (node (ref "U4") (pin "63") (pinfunction "PB14_63") (pintype "bidirectional"))
    )
    (net (code "109") (name "unconnected-(U4-TST-Pad40)") (class "Default")
      (node (ref "U4") (pin "40") (pinfunction "TST_40") (pintype "bidirectional"))
    )
  )
)
